# ir-kh.net
KiCad netlist of a schematic drawn in Altium Designer
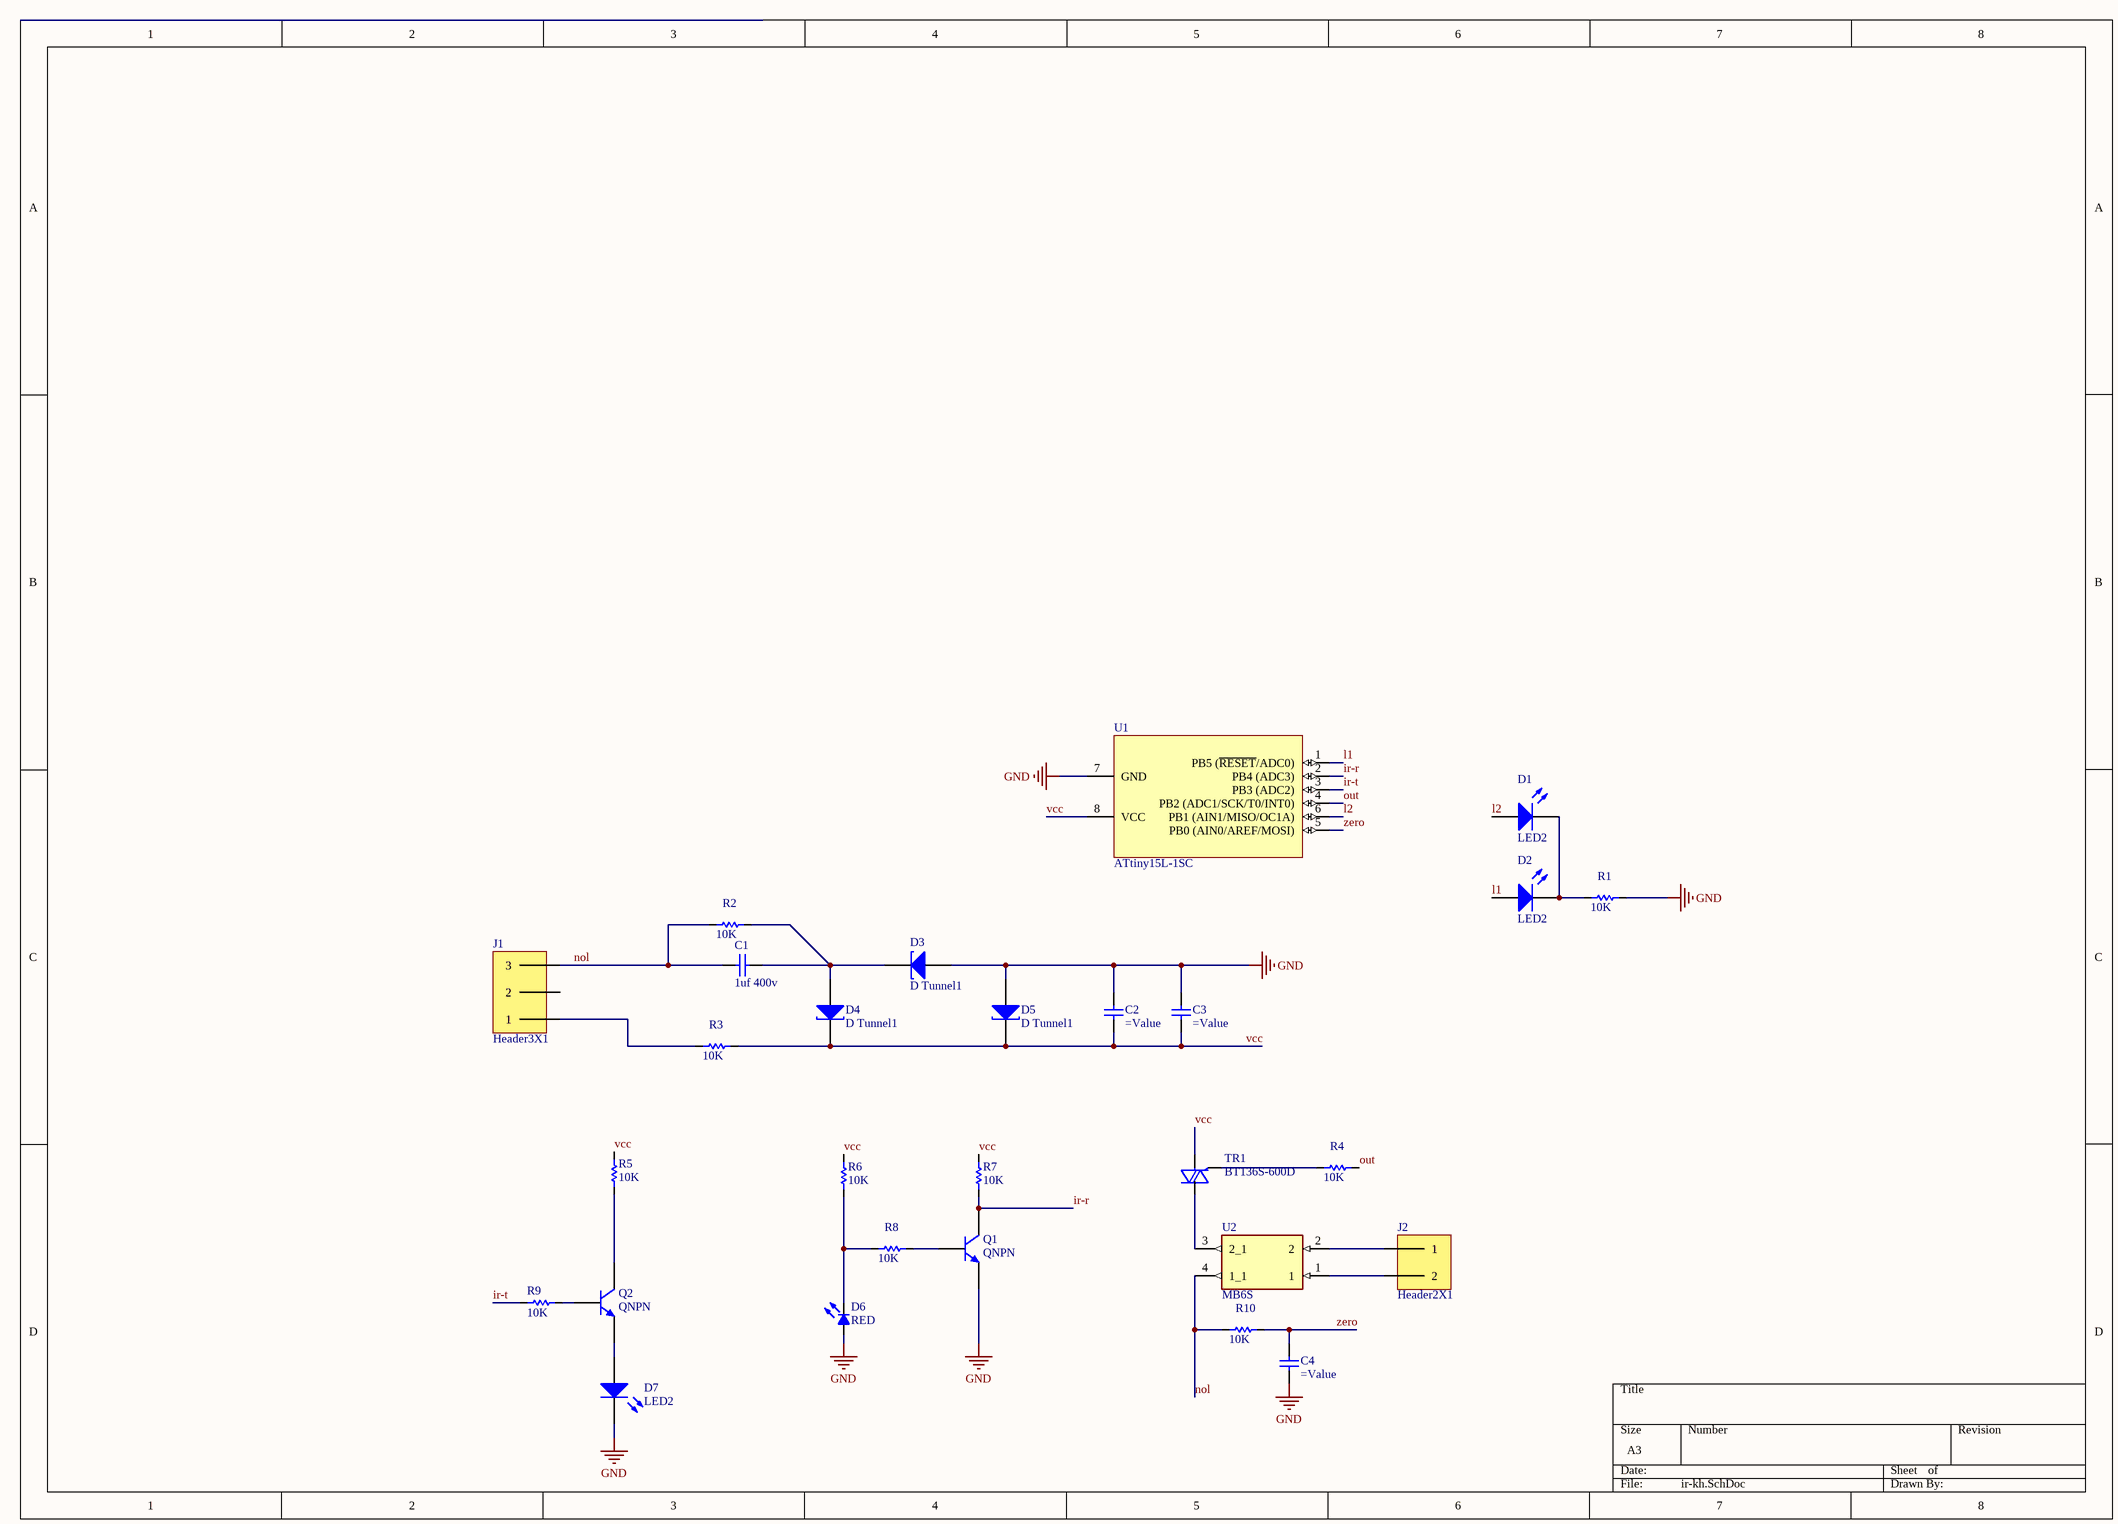
[diagram p0: ir-kh.SchDoc]

(export (version "E")
  (design (tool "Eeschema 10.0.6"))
  (components
    (comp (ref "C1")
      (value "1uf 400v")
      (footprint "1uf 400v")
      (description "Capacitor 24*9mm")
      (fields (field (name "DESIGNER") "Seyed Mohsen Ghasemain"))
      (libsource (lib "PicPars.com_usefully_Library") (part "1uf 400v"))
    )
    (comp (ref "C2")
      (value "~")
      (footprint "CAP 1206")
      (description "Capacitor")
      (libsource (lib "AltiumLib1") (part "Capacitor"))
    )
    (comp (ref "C3")
      (value "~")
      (footprint "CAP 1206")
      (description "Capacitor")
      (libsource (lib "AltiumLib1") (part "Capacitor"))
    )
    (comp (ref "C4")
      (value "~")
      (footprint "CAP 1206")
      (description "Capacitor")
      (libsource (lib "AltiumLib1") (part "Capacitor"))
    )
    (comp (ref "D1")
      (value "LED2")
      (footprint "3.2X1.6X1.1")
      (description "Typical RED, GREEN, YELLOW, AMBER GaAs LED")
      (fields (field (name "PUBLISHER") "Altium Limited"))
      (libsource (lib "Miscellaneous Devices") (part "LED2"))
    )
    (comp (ref "D2")
      (value "LED2")
      (footprint "3.2X1.6X1.1")
      (description "Typical RED, GREEN, YELLOW, AMBER GaAs LED")
      (fields (field (name "PUBLISHER") "Altium Limited"))
      (libsource (lib "Miscellaneous Devices") (part "LED2"))
    )
    (comp (ref "D3")
      (value "D Tunnel1")
      (footprint "3.2X1.6X1.1")
      (description "Tunnel Diode - RLC Model")
      (fields (field (name "PUBLISHER") "Altium Limited"))
      (libsource (lib "Miscellaneous Devices") (part "D Tunnel1"))
    )
    (comp (ref "D4")
      (value "D Tunnel1")
      (footprint "3.2X1.6X1.1")
      (description "Tunnel Diode - RLC Model")
      (fields (field (name "PUBLISHER") "Altium Limited"))
      (libsource (lib "Miscellaneous Devices") (part "D Tunnel1"))
    )
    (comp (ref "D5")
      (value "D Tunnel1")
      (footprint "3.2X1.6X1.1")
      (description "Tunnel Diode - RLC Model")
      (fields (field (name "PUBLISHER") "Altium Limited"))
      (libsource (lib "Miscellaneous Devices") (part "D Tunnel1"))
    )
    (comp (ref "D6")
      (value "MODEL")
      (footprint "LED-5mm")
      (description "Typical LED")
      (fields (field (name "COLOR") "RED"))
      (libsource (lib "AltiumLib1") (part "LED 5mm"))
    )
    (comp (ref "D7")
      (value "LED2")
      (footprint "3.2X1.6X1.1")
      (description "Typical RED, GREEN, YELLOW, AMBER GaAs LED")
      (fields (field (name "PUBLISHER") "Altium Limited"))
      (libsource (lib "Miscellaneous Devices") (part "LED2"))
    )
    (comp (ref "J1")
      (value "Header3X1")
      (footprint "HEADER 3X1")
      (libsource (lib "AltiumLib1") (part "Header3X1"))
    )
    (comp (ref "J2")
      (value "Header2X1")
      (footprint "Header 2X1")
      (libsource (lib "AltiumLib1") (part "Header2X1"))
    )
    (comp (ref "Q1")
      (value "QNPN")
      (footprint "SOT-23B_L")
      (description "NPN Bipolar Transistor")
      (fields (field (name "PUBLISHER") "Altium Limited"))
      (libsource (lib "Miscellaneous Devices") (part "QNPN"))
    )
    (comp (ref "Q2")
      (value "QNPN")
      (footprint "SOT-23B_L")
      (description "NPN Bipolar Transistor")
      (fields (field (name "PUBLISHER") "Altium Limited"))
      (libsource (lib "Miscellaneous Devices") (part "QNPN"))
    )
    (comp (ref "R1")
      (value "10K")
      (footprint "RES 1206 (3216X08L)")
      (description "Resistor")
      (fields (field (name "TOLERANCE") "5%") (field (name "POWER") "1/4 W"))
      (libsource (lib "AltiumLib1") (part "Resistor"))
    )
    (comp (ref "R2")
      (value "10K")
      (footprint "RES 1206 (3216X08L)")
      (description "Resistor")
      (fields (field (name "TOLERANCE") "5%") (field (name "POWER") "1/4 W"))
      (libsource (lib "AltiumLib1") (part "Resistor"))
    )
    (comp (ref "R3")
      (value "10K")
      (footprint "Res-(2/1)")
      (description "Resistor")
      (fields (field (name "TOLERANCE") "5%") (field (name "POWER") "1/4 W"))
      (libsource (lib "AltiumLib1") (part "Resistor"))
    )
    (comp (ref "R4")
      (value "10K")
      (footprint "RES 1206 (3216X08L)")
      (description "Resistor")
      (fields (field (name "TOLERANCE") "5%") (field (name "POWER") "1/4 W"))
      (libsource (lib "AltiumLib1") (part "Resistor"))
    )
    (comp (ref "R5")
      (value "10K")
      (footprint "RES 1206 (3216X08L)")
      (description "Resistor")
      (fields (field (name "TOLERANCE") "5%") (field (name "POWER") "1/4 W"))
      (libsource (lib "AltiumLib1") (part "Resistor"))
    )
    (comp (ref "R6")
      (value "10K")
      (footprint "RES 1206 (3216X08L)")
      (description "Resistor")
      (fields (field (name "TOLERANCE") "5%") (field (name "POWER") "1/4 W"))
      (libsource (lib "AltiumLib1") (part "Resistor"))
    )
    (comp (ref "R7")
      (value "10K")
      (footprint "RES 1206 (3216X08L)")
      (description "Resistor")
      (fields (field (name "TOLERANCE") "5%") (field (name "POWER") "1/4 W"))
      (libsource (lib "AltiumLib1") (part "Resistor"))
    )
    (comp (ref "R8")
      (value "10K")
      (footprint "RES 1206 (3216X08L)")
      (description "Resistor")
      (fields (field (name "TOLERANCE") "5%") (field (name "POWER") "1/4 W"))
      (libsource (lib "AltiumLib1") (part "Resistor"))
    )
    (comp (ref "R9")
      (value "10K")
      (footprint "RES 1206 (3216X08L)")
      (description "Resistor")
      (fields (field (name "TOLERANCE") "5%") (field (name "POWER") "1/4 W"))
      (libsource (lib "AltiumLib1") (part "Resistor"))
    )
    (comp (ref "R10")
      (value "10K")
      (footprint "RES 1206 (3216X08L)")
      (description "Resistor")
      (fields (field (name "TOLERANCE") "5%") (field (name "POWER") "1/4 W"))
      (libsource (lib "AltiumLib1") (part "Resistor"))
    )
    (comp (ref "TR1")
      (value "BT136S-600D")
      (footprint "SOT428")
      (description "TRIAC 600V 27A 3-Pin(2+Tab) DPAK")
      (fields (field (name "MF") "WeEn Semiconductor(Hong Kong)Co.,Limited"))
      (libsource (lib "BT136S-600D") (part "BT136S-600D"))
    )
    (comp (ref "U1")
      (value "ATtiny15L-1SC")
      (footprint "8S2_N")
      (description "8-Bit AVR Microcontroller with 1K Byte of Flash Memory")
      (fields (field (name "PUBLISHER") "Altium Limited"))
      (libsource (lib "Atmel Microcontroller 8-Bit AVR") (part "ATtiny15L-1SC"))
    )
    (comp (ref "U2")
      (value "MB6S")
      (footprint "SOIC245P670X270-4N")
      (description "Bridge Rectifier Single Phase Standard 600V Surface Mount 4-SOIC")
      (fields (field (name "MF") "ON Semiconductor") (field (name "DIGI-KEY_PART_NUMBER") "MB6SCT-ND"))
      (libsource (lib "MB6S") (part "MB6S"))
    )
  )
  (nets
    (net (code "1") (name "/ir-r") (class "Default")
      (node (ref "Q1") (pin "1") (pinfunction "C_1") (pintype "passive"))
      (node (ref "R7") (pin "2") (pinfunction "2_2") (pintype "passive"))
      (node (ref "U1") (pin "2") (pinfunction "PB4_(ADC3)_2") (pintype "bidirectional"))
    )
    (net (code "2") (name "/ir-t") (class "Default")
      (node (ref "R9") (pin "1") (pinfunction "1_1") (pintype "passive"))
      (node (ref "U1") (pin "3") (pinfunction "PB3_(ADC2)_3") (pintype "bidirectional"))
    )
    (net (code "3") (name "/l1") (class "Default")
      (node (ref "D2") (pin "1") (pinfunction "A_1") (pintype "passive"))
      (node (ref "U1") (pin "1") (pinfunction "PB5_(~{RESET}/ADC0)_1") (pintype "bidirectional"))
    )
    (net (code "4") (name "/l2") (class "Default")
      (node (ref "D1") (pin "1") (pinfunction "A_1") (pintype "passive"))
      (node (ref "U1") (pin "6") (pinfunction "PB1_(AIN1/MISO/OC1A)_6") (pintype "bidirectional"))
    )
    (net (code "5") (name "/nol") (class "Default")
      (node (ref "C1") (pin "1") (pinfunction "1_1") (pintype "passive"))
      (node (ref "J1") (pin "3") (pinfunction "3_3") (pintype "passive"))
      (node (ref "R10") (pin "1") (pinfunction "1_1") (pintype "passive"))
      (node (ref "R2") (pin "1") (pinfunction "1_1") (pintype "passive"))
      (node (ref "U2") (pin "4") (pinfunction "1_1_4") (pintype "output"))
    )
    (net (code "6") (name "/out") (class "Default")
      (node (ref "R4") (pin "2") (pinfunction "2_2") (pintype "passive"))
      (node (ref "U1") (pin "4") (pinfunction "PB2_(ADC1/SCK/T0/INT0)_4") (pintype "bidirectional"))
    )
    (net (code "7") (name "/vcc") (class "Default")
      (node (ref "C2") (pin "1") (pinfunction "+_1") (pintype "passive"))
      (node (ref "C3") (pin "1") (pinfunction "+_1") (pintype "passive"))
      (node (ref "D4") (pin "2") (pinfunction "K_2") (pintype "passive"))
      (node (ref "D5") (pin "2") (pinfunction "K_2") (pintype "passive"))
      (node (ref "R3") (pin "2") (pinfunction "2_2") (pintype "passive"))
      (node (ref "R5") (pin "2") (pinfunction "2_2") (pintype "passive"))
      (node (ref "R6") (pin "1") (pinfunction "1_1") (pintype "passive"))
      (node (ref "R7") (pin "1") (pinfunction "1_1") (pintype "passive"))
      (node (ref "TR1") (pin "1") (pinfunction "A1_1") (pintype "passive"))
      (node (ref "U1") (pin "8") (pinfunction "VCC_8") (pintype "power_in"))
    )
    (net (code "8") (name "/zero") (class "Default")
      (node (ref "C4") (pin "2") (pinfunction "-_2") (pintype "passive"))
      (node (ref "R10") (pin "2") (pinfunction "2_2") (pintype "passive"))
      (node (ref "U1") (pin "5") (pinfunction "PB0_(AIN0/AREF/MOSI)_5") (pintype "bidirectional"))
    )
    (net (code "9") (name "GND") (class "Default")
      (node (ref "C2") (pin "2") (pinfunction "-_2") (pintype "passive"))
      (node (ref "C3") (pin "2") (pinfunction "-_2") (pintype "passive"))
      (node (ref "C4") (pin "1") (pinfunction "+_1") (pintype "passive"))
      (node (ref "D3") (pin "1") (pinfunction "A_1") (pintype "passive"))
      (node (ref "D5") (pin "1") (pinfunction "A_1") (pintype "passive"))
      (node (ref "D6") (pin "1") (pinfunction "A_1") (pintype "passive"))
      (node (ref "D7") (pin "2") (pinfunction "K_2") (pintype "passive"))
      (node (ref "Q1") (pin "3") (pinfunction "E_3") (pintype "passive"))
      (node (ref "R1") (pin "2") (pinfunction "2_2") (pintype "passive"))
      (node (ref "U1") (pin "7") (pinfunction "GND_7") (pintype "power_in"))
    )
    (net (code "10") (name "Net-(D1-K)") (class "Default")
      (node (ref "D1") (pin "2") (pinfunction "K_2") (pintype "passive"))
      (node (ref "D2") (pin "2") (pinfunction "K_2") (pintype "passive"))
      (node (ref "R1") (pin "1") (pinfunction "1_1") (pintype "passive"))
    )
    (net (code "11") (name "Net-(D3-K)") (class "Default")
      (node (ref "C1") (pin "2") (pinfunction "2_2") (pintype "passive"))
      (node (ref "D3") (pin "2") (pinfunction "K_2") (pintype "passive"))
      (node (ref "D4") (pin "1") (pinfunction "A_1") (pintype "passive"))
      (node (ref "R2") (pin "2") (pinfunction "2_2") (pintype "passive"))
    )
    (net (code "12") (name "Net-(D6-K)") (class "Default")
      (node (ref "D6") (pin "2") (pinfunction "K_2") (pintype "passive"))
      (node (ref "R6") (pin "2") (pinfunction "2_2") (pintype "passive"))
      (node (ref "R8") (pin "1") (pinfunction "1_1") (pintype "passive"))
    )
    (net (code "13") (name "Net-(D7-A)") (class "Default")
      (node (ref "D7") (pin "1") (pinfunction "A_1") (pintype "passive"))
      (node (ref "Q2") (pin "3") (pinfunction "E_3") (pintype "passive"))
    )
    (net (code "14") (name "Net-(J1-Pad1)") (class "Default")
      (node (ref "J1") (pin "1") (pinfunction "1_1") (pintype "passive"))
      (node (ref "R3") (pin "1") (pinfunction "1_1") (pintype "passive"))
    )
    (net (code "15") (name "Net-(J2-Pad1)") (class "Default")
      (node (ref "J2") (pin "1") (pinfunction "1_1") (pintype "passive"))
      (node (ref "U2") (pin "2") (pinfunction "2_2") (pintype "input"))
    )
    (net (code "16") (name "Net-(J2-Pad2)") (class "Default")
      (node (ref "J2") (pin "2") (pinfunction "2_2") (pintype "passive"))
      (node (ref "U2") (pin "1") (pinfunction "1_1") (pintype "input"))
    )
    (net (code "17") (name "Net-(Q1-B)") (class "Default")
      (node (ref "Q1") (pin "2") (pinfunction "B_2") (pintype "passive"))
      (node (ref "R8") (pin "2") (pinfunction "2_2") (pintype "passive"))
    )
    (net (code "18") (name "Net-(Q2-B)") (class "Default")
      (node (ref "Q2") (pin "2") (pinfunction "B_2") (pintype "passive"))
      (node (ref "R9") (pin "2") (pinfunction "2_2") (pintype "passive"))
    )
    (net (code "19") (name "Net-(Q2-C)") (class "Default")
      (node (ref "Q2") (pin "1") (pinfunction "C_1") (pintype "passive"))
      (node (ref "R5") (pin "1") (pinfunction "1_1") (pintype "passive"))
    )
    (net (code "20") (name "Net-(TR1-A2)") (class "Default")
      (node (ref "TR1") (pin "MB") (pinfunction "A2_MB") (pintype "passive"))
      (node (ref "U2") (pin "3") (pinfunction "2_1_3") (pintype "output"))
    )
    (net (code "21") (name "Net-(TR1-G)") (class "Default")
      (node (ref "R4") (pin "1") (pinfunction "1_1") (pintype "passive"))
      (node (ref "TR1") (pin "3") (pinfunction "G_3") (pintype "passive"))
    )
    (net (code "22") (name "unconnected-(J1-Pad2)") (class "Default")
      (node (ref "J1") (pin "2") (pinfunction "2_2") (pintype "passive"))
    )
  )
)
